# power.net
KiCad netlist of a schematic drawn in Altium Designer
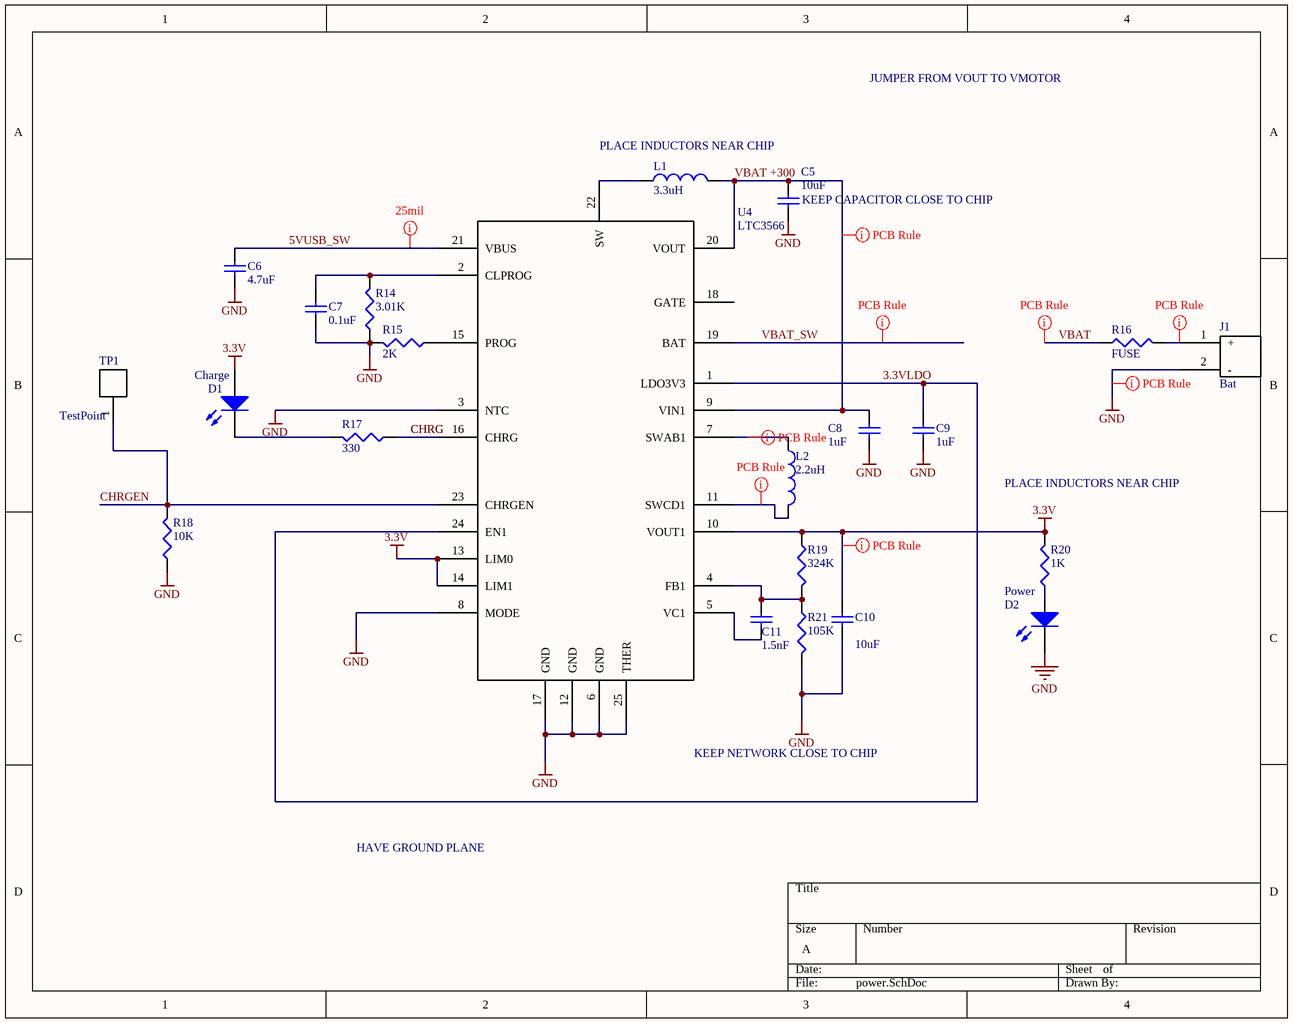
[diagram p0: power.SchDoc]

(export (version "E")
  (design (tool "Eeschema 10.0.6"))
  (components
    (comp (ref "C5")
      (value "10uF")
      (footprint "CAPC1608L")
      (description "Capacitor")
      (fields (field (name "Comment") "Cap") (field (name "PUBLISHER") "Altium Limited"))
      (libsource (lib "Miscellaneous Devices") (part "Cap"))
    )
    (comp (ref "C6")
      (value "4.7uF")
      (footprint "CAPC1608L")
      (description "Capacitor")
      (fields (field (name "Comment") "Cap") (field (name "PUBLISHER") "Altium Limited"))
      (libsource (lib "Miscellaneous Devices") (part "Cap"))
    )
    (comp (ref "C7")
      (value "0.1uF")
      (footprint "CAPC1005L")
      (description "Capacitor")
      (fields (field (name "Comment") "Cap") (field (name "PUBLISHER") "Altium Limited"))
      (libsource (lib "Miscellaneous Devices") (part "Cap"))
    )
    (comp (ref "C8")
      (value "1uF")
      (footprint "CAPC1608L")
      (description "Capacitor")
      (fields (field (name "Comment") "Cap") (field (name "PUBLISHER") "Altium Limited"))
      (libsource (lib "Miscellaneous Devices") (part "Cap"))
    )
    (comp (ref "C9")
      (value "1uF")
      (footprint "CAPC1608L")
      (description "Capacitor")
      (fields (field (name "Comment") "Cap") (field (name "PUBLISHER") "Altium Limited"))
      (libsource (lib "Miscellaneous Devices") (part "Cap"))
    )
    (comp (ref "C10")
      (value "10uF")
      (footprint "CAPC1608L")
      (description "Capacitor")
      (fields (field (name "Comment") "Cap") (field (name "PUBLISHER") "Altium Limited"))
      (libsource (lib "Miscellaneous Devices") (part "Cap"))
    )
    (comp (ref "C11")
      (value "1.5nF")
      (footprint "CAPC1005L")
      (description "Capacitor")
      (fields (field (name "Comment") "Cap") (field (name "PUBLISHER") "Altium Limited"))
      (libsource (lib "Miscellaneous Devices") (part "Cap"))
    )
    (comp (ref "D1")
      (value "Charge")
      (footprint "INDC2012L")
      (description "Typical RED, GREEN, YELLOW, AMBER GaAs LED")
      (fields (field (name "PUBLISHER") "Altium Limited"))
      (libsource (lib "Miscellaneous Devices") (part "LED2"))
    )
    (comp (ref "D2")
      (value "Power")
      (footprint "INDC2012L")
      (description "Typical RED, GREEN, YELLOW, AMBER GaAs LED")
      (fields (field (name "PUBLISHER") "Altium Limited"))
      (libsource (lib "Miscellaneous Devices") (part "LED2"))
    )
    (comp (ref "J1")
      (value "Bat")
      (footprint "BatteryConnJST")
      (libsource (lib "mrone") (part "BatteryConnJST"))
    )
    (comp (ref "L1") (value "3.3uH") (footprint "Inductor-Power") (libsource (lib "mrone") (part "Inductor")))
    (comp (ref "L2") (value "2.2uH") (footprint "Inductor-Power") (libsource (lib "mrone") (part "Inductor")))
    (comp (ref "R14")
      (value "3.01K")
      (footprint "RESC1608L")
      (description "Resistor")
      (fields (field (name "Comment") "Res3") (field (name "PUBLISHER") "Altium Limited"))
      (libsource (lib "Miscellaneous Devices") (part "Res3"))
    )
    (comp (ref "R15")
      (value "2K")
      (footprint "RESC1608L")
      (description "Resistor")
      (fields (field (name "Comment") "Res3") (field (name "PUBLISHER") "Altium Limited"))
      (libsource (lib "Miscellaneous Devices") (part "Res3"))
    )
    (comp (ref "R16")
      (value "FUSE")
      (footprint "RESC3225L")
      (description "Resistor")
      (fields (field (name "Comment") "Res3") (field (name "PUBLISHER") "Altium Limited"))
      (libsource (lib "Miscellaneous Devices") (part "Res3"))
    )
    (comp (ref "R17")
      (value "330")
      (footprint "RESC1608L")
      (description "Resistor")
      (fields (field (name "Comment") "Res3") (field (name "PUBLISHER") "Altium Limited"))
      (libsource (lib "Miscellaneous Devices") (part "Res3"))
    )
    (comp (ref "R18")
      (value "10K")
      (footprint "RESC1608L")
      (description "Resistor")
      (fields (field (name "Comment") "Res3") (field (name "PUBLISHER") "Altium Limited"))
      (libsource (lib "Miscellaneous Devices") (part "Res3"))
    )
    (comp (ref "R19")
      (value "324K")
      (footprint "RESC1608L")
      (description "Resistor")
      (fields (field (name "Comment") "Res3") (field (name "PUBLISHER") "Altium Limited"))
      (libsource (lib "Miscellaneous Devices") (part "Res3"))
    )
    (comp (ref "R20")
      (value "1K")
      (footprint "RESC1608L")
      (description "Resistor")
      (fields (field (name "Comment") "Res3") (field (name "PUBLISHER") "Altium Limited"))
      (libsource (lib "Miscellaneous Devices") (part "Res3"))
    )
    (comp (ref "R21")
      (value "105K")
      (footprint "RESC1608L")
      (description "Resistor")
      (fields (field (name "Comment") "Res3") (field (name "PUBLISHER") "Altium Limited"))
      (libsource (lib "Miscellaneous Devices") (part "Res3"))
    )
    (comp (ref "TP1")
      (value "TestPoint")
      (footprint "TestPoint")
      (libsource (lib "mrone") (part "TestPoint"))
    )
    (comp (ref "U4")
      (value "LTC3566")
      (footprint "QFN-24")
      (libsource (lib "Schematic Components") (part "LTC3566"))
    )
  )
  (nets
    (net (code "1") (name "/3.3VLDO") (class "Default")
      (node (ref "C9") (pin "1") (pinfunction "1_1") (pintype "passive"))
      (node (ref "U4") (pin "1") (pinfunction "LDO3V3_1") (pintype "passive"))
      (node (ref "U4") (pin "24") (pinfunction "EN1_24") (pintype "passive"))
    )
    (net (code "2") (name "/5VUSB_SW") (class "Default")
      (node (ref "C6") (pin "2") (pinfunction "2_2") (pintype "passive"))
      (node (ref "U4") (pin "21") (pinfunction "VBUS_21") (pintype "passive"))
    )
    (net (code "3") (name "/CHRG") (class "Default")
      (node (ref "R17") (pin "1") (pinfunction "1_1") (pintype "passive"))
      (node (ref "U4") (pin "16") (pinfunction "CHRG_16") (pintype "passive"))
    )
    (net (code "4") (name "/CHRGEN") (class "Default")
      (node (ref "R18") (pin "2") (pinfunction "2_2") (pintype "passive"))
      (node (ref "TP1") (pin "1") (pintype "passive"))
      (node (ref "U4") (pin "23") (pinfunction "CHRGEN_23") (pintype "passive"))
    )
    (net (code "5") (name "/VBAT") (class "Default")
      (node (ref "R16") (pin "1") (pinfunction "1_1") (pintype "passive"))
    )
    (net (code "6") (name "/VBAT +300") (class "Default")
      (node (ref "C5") (pin "2") (pinfunction "2_2") (pintype "passive"))
      (node (ref "C8") (pin "1") (pinfunction "1_1") (pintype "passive"))
      (node (ref "L1") (pin "2") (pinfunction "2_2") (pintype "passive"))
      (node (ref "U4") (pin "20") (pinfunction "VOUT_20") (pintype "passive"))
      (node (ref "U4") (pin "9") (pinfunction "VIN1_9") (pintype "passive"))
    )
    (net (code "7") (name "/VBAT_SW") (class "Default")
      (node (ref "U4") (pin "19") (pinfunction "BAT_19") (pintype "passive"))
    )
    (net (code "8") (name "3.3V") (class "Default")
      (node (ref "C10") (pin "2") (pinfunction "2_2") (pintype "passive"))
      (node (ref "D1") (pin "1") (pinfunction "A_1") (pintype "passive"))
      (node (ref "R19") (pin "1") (pinfunction "1_1") (pintype "passive"))
      (node (ref "R20") (pin "2") (pinfunction "2_2") (pintype "passive"))
      (node (ref "U4") (pin "10") (pinfunction "VOUT1_10") (pintype "passive"))
      (node (ref "U4") (pin "13") (pinfunction "LIM0_13") (pintype "passive"))
      (node (ref "U4") (pin "14") (pinfunction "LIM1_14") (pintype "passive"))
    )
    (net (code "9") (name "GND") (class "Default")
      (node (ref "C10") (pin "1") (pinfunction "1_1") (pintype "passive"))
      (node (ref "C5") (pin "1") (pinfunction "1_1") (pintype "passive"))
      (node (ref "C6") (pin "1") (pinfunction "1_1") (pintype "passive"))
      (node (ref "C7") (pin "1") (pinfunction "1_1") (pintype "passive"))
      (node (ref "C8") (pin "2") (pinfunction "2_2") (pintype "passive"))
      (node (ref "C9") (pin "2") (pinfunction "2_2") (pintype "passive"))
      (node (ref "D2") (pin "2") (pinfunction "K_2") (pintype "passive"))
      (node (ref "J1") (pin "2") (pinfunction "-_2") (pintype "passive"))
      (node (ref "R14") (pin "1") (pinfunction "1_1") (pintype "passive"))
      (node (ref "R15") (pin "2") (pinfunction "2_2") (pintype "passive"))
      (node (ref "R18") (pin "1") (pinfunction "1_1") (pintype "passive"))
      (node (ref "R21") (pin "2") (pinfunction "2_2") (pintype "passive"))
      (node (ref "U4") (pin "12") (pinfunction "GND_12") (pintype "passive"))
      (node (ref "U4") (pin "17") (pinfunction "GND_17") (pintype "passive"))
      (node (ref "U4") (pin "25") (pinfunction "THER_25") (pintype "passive"))
      (node (ref "U4") (pin "3") (pinfunction "NTC_3") (pintype "passive"))
      (node (ref "U4") (pin "6") (pinfunction "GND_6") (pintype "passive"))
      (node (ref "U4") (pin "8") (pinfunction "MODE_8") (pintype "passive"))
    )
    (net (code "10") (name "Net-(D1-K)") (class "Default")
      (node (ref "D1") (pin "2") (pinfunction "K_2") (pintype "passive"))
      (node (ref "R17") (pin "2") (pinfunction "2_2") (pintype "passive"))
    )
    (net (code "11") (name "Net-(D2-A)") (class "Default")
      (node (ref "D2") (pin "1") (pinfunction "A_1") (pintype "passive"))
      (node (ref "R20") (pin "1") (pinfunction "1_1") (pintype "passive"))
    )
    (net (code "12") (name "Net-(J1-+)") (class "Default")
      (node (ref "J1") (pin "1") (pinfunction "+_1") (pintype "passive"))
      (node (ref "R16") (pin "2") (pinfunction "2_2") (pintype "passive"))
    )
    (net (code "13") (name "Net-(U4-CLPROG)") (class "Default")
      (node (ref "C7") (pin "2") (pinfunction "2_2") (pintype "passive"))
      (node (ref "R14") (pin "2") (pinfunction "2_2") (pintype "passive"))
      (node (ref "U4") (pin "2") (pinfunction "CLPROG_2") (pintype "passive"))
    )
    (net (code "14") (name "Net-(U4-FB1)") (class "Default")
      (node (ref "C11") (pin "1") (pinfunction "1_1") (pintype "passive"))
      (node (ref "R19") (pin "2") (pinfunction "2_2") (pintype "passive"))
      (node (ref "R21") (pin "1") (pinfunction "1_1") (pintype "passive"))
      (node (ref "U4") (pin "4") (pinfunction "FB1_4") (pintype "passive"))
    )
    (net (code "15") (name "Net-(U4-PROG)") (class "Default")
      (node (ref "R15") (pin "1") (pinfunction "1_1") (pintype "passive"))
      (node (ref "U4") (pin "15") (pinfunction "PROG_15") (pintype "passive"))
    )
    (net (code "16") (name "Net-(U4-SW)") (class "Default")
      (node (ref "L1") (pin "1") (pinfunction "1_1") (pintype "passive"))
      (node (ref "U4") (pin "22") (pinfunction "SW_22") (pintype "passive"))
    )
    (net (code "17") (name "Net-(U4-SWAB1)") (class "Default")
      (node (ref "L2") (pin "1") (pinfunction "1_1") (pintype "passive"))
      (node (ref "U4") (pin "7") (pinfunction "SWAB1_7") (pintype "passive"))
    )
    (net (code "18") (name "Net-(U4-SWCD1)") (class "Default")
      (node (ref "L2") (pin "2") (pinfunction "2_2") (pintype "passive"))
      (node (ref "U4") (pin "11") (pinfunction "SWCD1_11") (pintype "passive"))
    )
    (net (code "19") (name "Net-(U4-VC1)") (class "Default")
      (node (ref "C11") (pin "2") (pinfunction "2_2") (pintype "passive"))
      (node (ref "U4") (pin "5") (pinfunction "VC1_5") (pintype "passive"))
    )
    (net (code "20") (name "unconnected-(U4-GATE-Pad18)") (class "Default")
      (node (ref "U4") (pin "18") (pinfunction "GATE_18") (pintype "passive"))
    )
  )
)
